# MCU_INTERFACE.net
KiCad netlist of a schematic drawn in Altium Designer
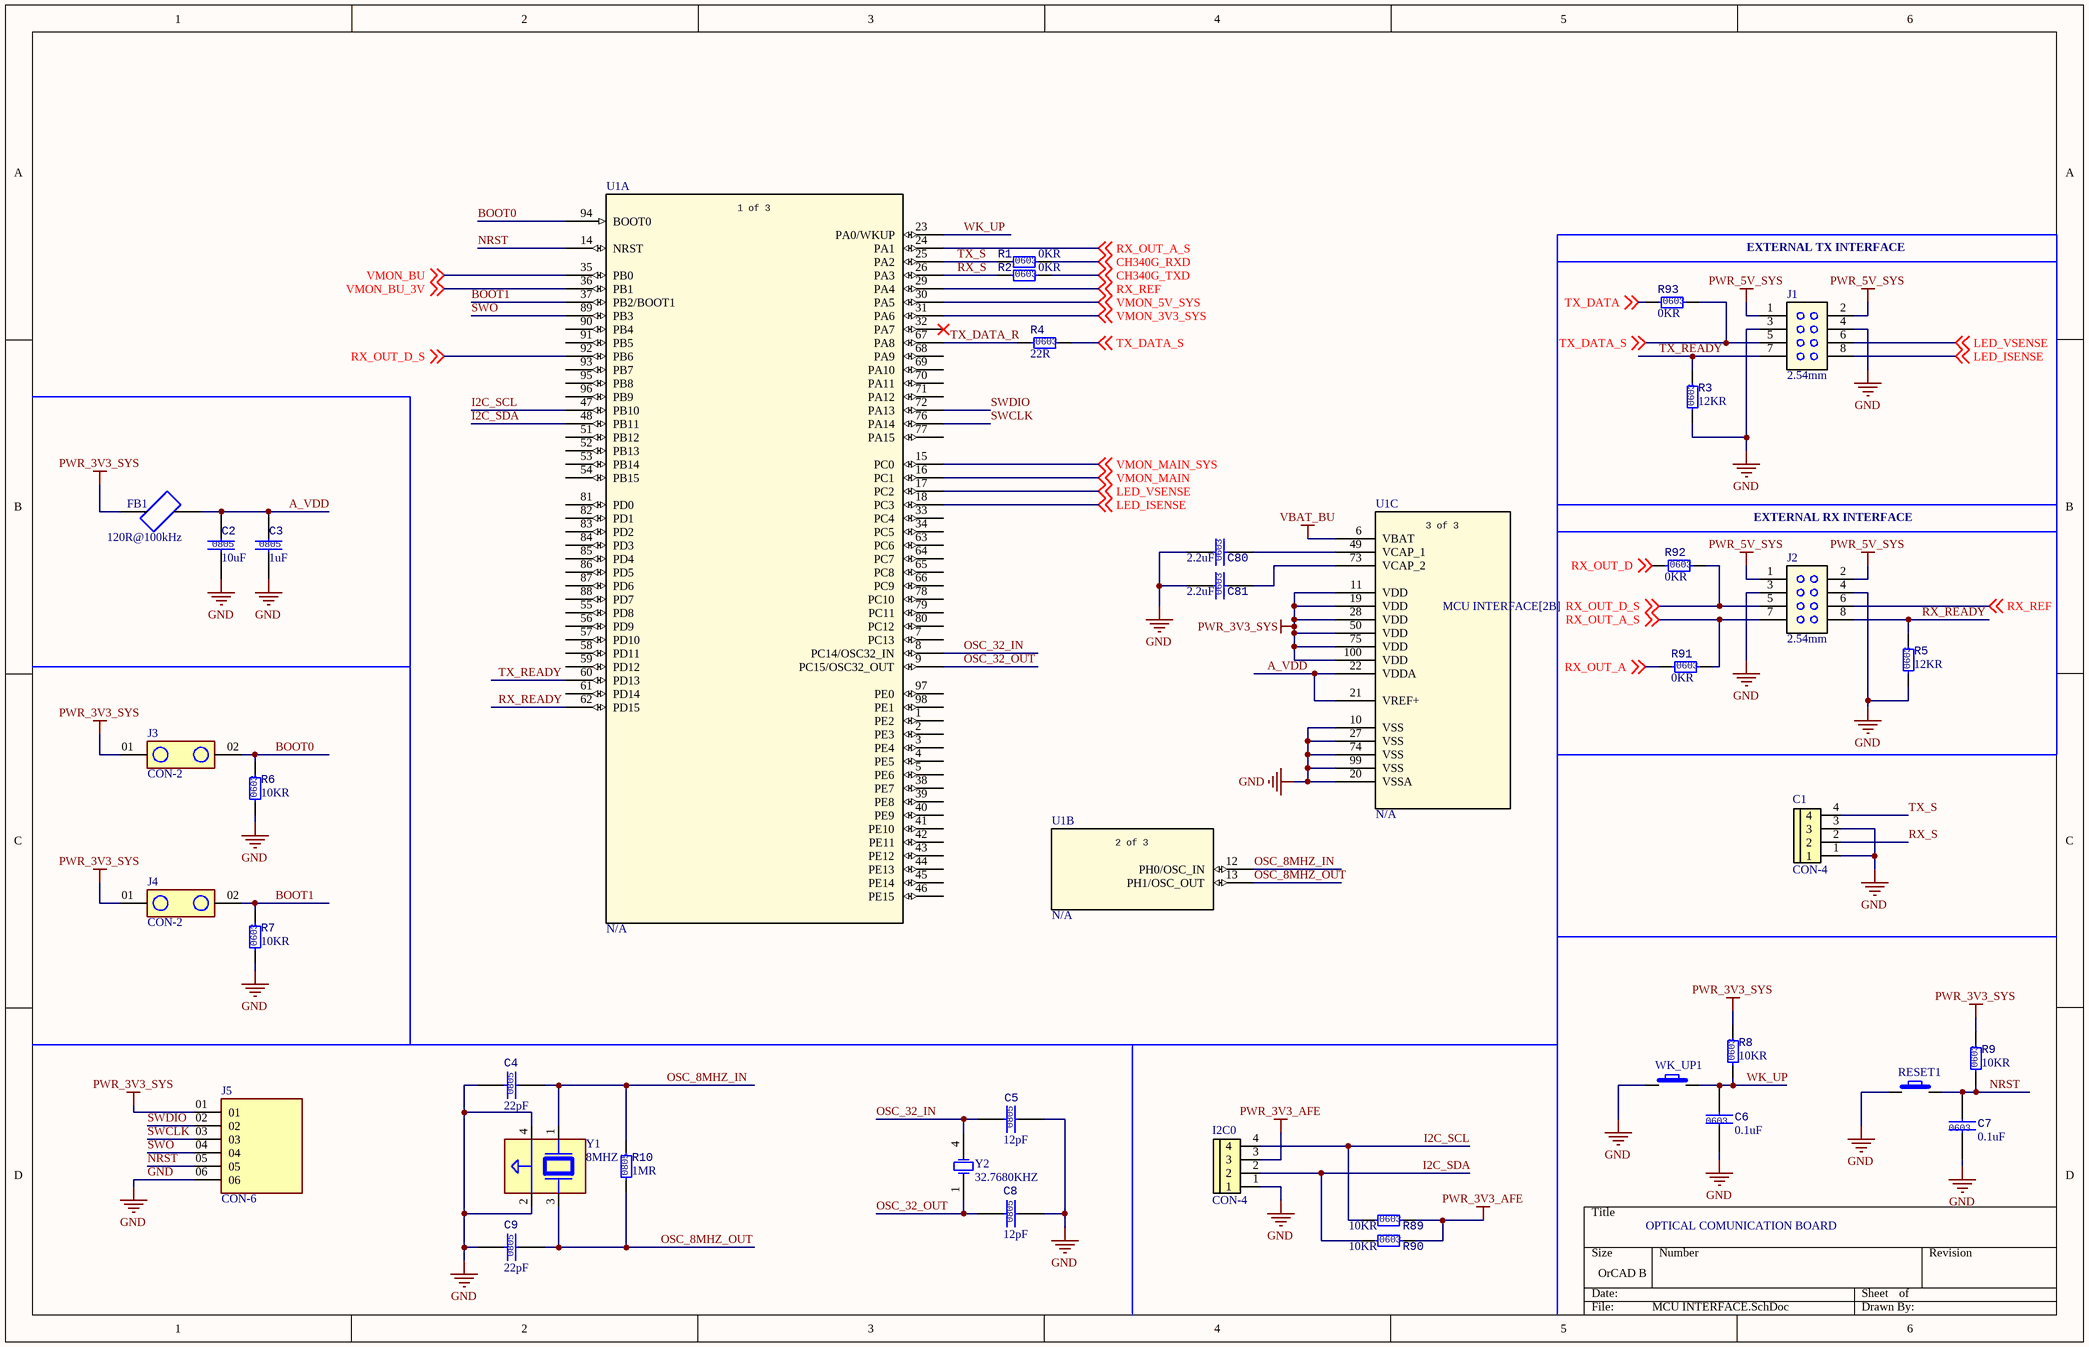
[diagram p0: MCU INTERFACE.SchDoc]

(export (version "E")
  (design (tool "Eeschema 10.0.6"))
  (components
    (comp (ref "C1")
      (value "CON-4")
      (footprint "CON-4")
      (description "Hàng Rào Đực Đơn 2.54mm 40 Chân 1 Hàng Cao 11.2mm Xuyên Lỗ")
      (fields (field (name "Comment") "CONNECTOR_4"))
      (libsource (lib "Database_Libs1") (part "CON-4"))
    )
    (comp (ref "C2")
      (value "10uF")
      (footprint "CAPCER 0603 SMD")
      (description "CAPACITOR SMD 10uF 25V 10% 0805")
      (fields (field (name "SIZE") "0805") (field (name "TOLERANCE") "10%"))
      (libsource (lib "Database_Libs1") (part "CAPACITOR"))
    )
    (comp (ref "C3")
      (value "1uF")
      (footprint "CAPCER 0805 SMD")
      (description "CAPACITOR SMD 1uF 16V 10% 0805")
      (fields (field (name "SIZE") "0805") (field (name "TOLERANCE") "10%"))
      (libsource (lib "Database_Libs1") (part "CAPACITOR"))
    )
    (comp (ref "C4")
      (value "22pF")
      (footprint "CAPCER 0805 SMD")
      (description "CAPACITOR SMD 22pF 50V 10% 0805")
      (fields (field (name "SIZE") "0805") (field (name "TOLERANCE") "10%") (field (name "Comment") "22uF"))
      (libsource (lib "Database_Libs1") (part "CAPACITOR"))
    )
    (comp (ref "C5")
      (value "12pF")
      (footprint "CAPCER 0805 SMD")
      (description "CAPACITOR SMD 12pF 50V 10% 0805")
      (fields (field (name "SIZE") "0805") (field (name "TOLERANCE") "10%"))
      (libsource (lib "Database_Libs1") (part "CAPACITOR"))
    )
    (comp (ref "C6")
      (value "0.1uF")
      (footprint "CAPCER 0805 SMD")
      (description "CAPACITOR SMD 0.1uF 50V 10% 0603")
      (fields (field (name "SIZE") "0603") (field (name "TOLERANCE") "10%"))
      (libsource (lib "Database_Libs1") (part "CAPACITOR"))
    )
    (comp (ref "C7")
      (value "0.1uF")
      (footprint "CAPCER 0805 SMD")
      (description "CAPACITOR SMD 0.1uF 50V 10% 0603")
      (fields (field (name "SIZE") "0603") (field (name "TOLERANCE") "10%"))
      (libsource (lib "Database_Libs1") (part "CAPACITOR"))
    )
    (comp (ref "C8")
      (value "12pF")
      (footprint "CAPCER 0805 SMD")
      (description "CAPACITOR SMD 12pF 50V 10% 0805")
      (fields (field (name "SIZE") "0805") (field (name "TOLERANCE") "10%"))
      (libsource (lib "Database_Libs1") (part "CAPACITOR"))
    )
    (comp (ref "C9")
      (value "22pF")
      (footprint "CAPCER 0805 SMD")
      (description "CAPACITOR SMD 22pF 50V 10% 0805")
      (fields (field (name "SIZE") "0805") (field (name "TOLERANCE") "10%") (field (name "Comment") "22uF"))
      (libsource (lib "Database_Libs1") (part "CAPACITOR"))
    )
    (comp (ref "C80")
      (value "2.2uF")
      (footprint "CAPCER 0603 SMD")
      (fields (field (name "SIZE") "0603"))
      (libsource (lib "Database_Libs2") (part "CAPACITOR"))
    )
    (comp (ref "C81")
      (value "2.2uF")
      (footprint "CAPCER 0603 SMD")
      (fields (field (name "SIZE") "0603"))
      (libsource (lib "Database_Libs2") (part "CAPACITOR"))
    )
    (comp (ref "FB1")
      (value "120R@100kHz")
      (footprint "FB 0805")
      (description "CBW201209U121T Ferrite Beads 2A 120 Ohm 0805")
      (libsource (lib "Database_Libs1") (part "FB"))
    )
    (comp (ref "I2C0")
      (value "CON-4")
      (footprint "CON-4")
      (description "Hàng Rào Đực Đơn 2.54mm 40 Chân 1 Hàng Cao 11.2mm Xuyên Lỗ")
      (fields (field (name "Comment") "CONNECTOR_4"))
      (libsource (lib "Database_Libs1") (part "CON-4"))
    )
    (comp (ref "J1")
      (value "2.54mm")
      (footprint "HD_2X4_2P54_M_V")
      (fields (field (name "Comment") "HD_2X4_M_V"))
      (libsource (lib "Database_Libs2") (part "HD_2X4_8POS"))
    )
    (comp (ref "J2")
      (value "2.54mm")
      (footprint "HD_2X4_2P54_M_V")
      (fields (field (name "Comment") "HD_2X4_M_V"))
      (libsource (lib "Database_Libs2") (part "HD_2X4_8POS"))
    )
    (comp (ref "J3")
      (value "CON-2")
      (footprint "CON-2")
      (description "Hàng Rào Đực Đơn 2.54mm 40 Chân 1 Hàng Cao 11.2mm Xuyên Lỗ")
      (fields (field (name "Comment") "CONNECTOR_2"))
      (libsource (lib "Database_Libs1") (part "CON-2"))
    )
    (comp (ref "J4")
      (value "CON-2")
      (footprint "CON-2")
      (description "Hàng Rào Đực Đơn 2.54mm 40 Chân 1 Hàng Cao 11.2mm Xuyên Lỗ")
      (fields (field (name "Comment") "CONNECTOR_2"))
      (libsource (lib "Database_Libs1") (part "CON-2"))
    )
    (comp (ref "J5")
      (value "CON-6")
      (footprint "CON-6")
      (description "Hàng Rào Đực Đơn 2.54mm 40 Chân 1 Hàng Cao 11.2mm Xuyên Lỗ")
      (fields (field (name "Comment") "CONNECTOR_6"))
      (libsource (lib "Database_Libs1") (part "CON-6"))
    )
    (comp (ref "R1")
      (value "0KR")
      (footprint "RESC 0603(1608) SMD")
      (description "RESISTOR SMD 0KR OHM 1% 100mW 0603")
      (fields (field (name "SIZE") "0603") (field (name "TOLERANCE") "1%") (field (name "Comment") "0R"))
      (libsource (lib "Database_Libs1") (part "RESISTOR"))
    )
    (comp (ref "R2")
      (value "0KR")
      (footprint "RESC 0603(1608) SMD")
      (description "RESISTOR SMD 0KR OHM 1% 100mW 0603")
      (fields (field (name "SIZE") "0603") (field (name "TOLERANCE") "1%") (field (name "Comment") "0R"))
      (libsource (lib "Database_Libs1") (part "RESISTOR"))
    )
    (comp (ref "R3")
      (value "12KR")
      (footprint "RESC 0603(1608) SMD")
      (description "RESISTOR SMD 12KR OHM 1% 100mW 0603")
      (fields (field (name "SIZE") "0603") (field (name "TOLERANCE") "1%"))
      (libsource (lib "") (part "RESISTOR_1"))
    )
    (comp (ref "R4")
      (value "22R")
      (footprint "RESC 0603(1608) SMD")
      (fields (field (name "SIZE") "0603"))
      (libsource (lib "Database_Libs2") (part "RESISTOR"))
    )
    (comp (ref "R5")
      (value "12KR")
      (footprint "RESC 0603(1608) SMD")
      (description "RESISTOR SMD 12KR OHM 1% 100mW 0603")
      (fields (field (name "SIZE") "0603") (field (name "TOLERANCE") "1%"))
      (libsource (lib "") (part "RESISTOR_1"))
    )
    (comp (ref "R6")
      (value "10KR")
      (footprint "RESC 0603(1608) SMD")
      (description "RESISTOR SMD 10KR OHM 1% 100mW 0603")
      (fields (field (name "SIZE") "0603") (field (name "TOLERANCE") "1%"))
      (libsource (lib "") (part "RESISTOR_1"))
    )
    (comp (ref "R7")
      (value "10KR")
      (footprint "RESC 0603(1608) SMD")
      (description "RESISTOR SMD 10KR OHM 1% 100mW 0603")
      (fields (field (name "SIZE") "0603") (field (name "TOLERANCE") "1%"))
      (libsource (lib "") (part "RESISTOR_1"))
    )
    (comp (ref "R8")
      (value "10KR")
      (footprint "RESC 0603(1608) SMD")
      (description "RESISTOR SMD 10KR OHM 1% 100mW 0603")
      (fields (field (name "SIZE") "0603") (field (name "TOLERANCE") "1%"))
      (libsource (lib "") (part "RESISTOR_1"))
    )
    (comp (ref "R9")
      (value "10KR")
      (footprint "RESC 0603(1608) SMD")
      (description "RESISTOR SMD 10KR OHM 1% 100mW 0603")
      (fields (field (name "SIZE") "0603") (field (name "TOLERANCE") "1%"))
      (libsource (lib "") (part "RESISTOR_1"))
    )
    (comp (ref "R10")
      (value "1MR")
      (footprint "CAPCER 0805 SMD")
      (description "RESISTOR SMD 1 MOHM 1% 100mW 0805")
      (fields
        (field (name "SIZE") "0805")
        (field (name "TOLERANCE") "1%")
        (field (name "Comment") "Điện Trở 1 MOhm 0805 1%")
      )
      (libsource (lib "") (part "RESISTOR_1"))
    )
    (comp (ref "R89")
      (value "10KR")
      (footprint "RESC 0603(1608) SMD")
      (description "RESISTOR SMD 10KR OHM 1% 100mW 0603")
      (fields (field (name "SIZE") "0603") (field (name "TOLERANCE") "1%"))
      (libsource (lib "Database_Libs1") (part "RESISTOR"))
    )
    (comp (ref "R90")
      (value "10KR")
      (footprint "RESC 0603(1608) SMD")
      (description "RESISTOR SMD 10KR OHM 1% 100mW 0603")
      (fields (field (name "SIZE") "0603") (field (name "TOLERANCE") "1%"))
      (libsource (lib "Database_Libs1") (part "RESISTOR"))
    )
    (comp (ref "R91")
      (value "0KR")
      (footprint "RESC 0603(1608) SMD")
      (description "RESISTOR SMD 0KR OHM 1% 100mW 0603")
      (fields (field (name "SIZE") "0603") (field (name "TOLERANCE") "1%") (field (name "Comment") "0R"))
      (libsource (lib "Database_Libs1") (part "RESISTOR"))
    )
    (comp (ref "R92")
      (value "0KR")
      (footprint "RESC 0603(1608) SMD")
      (description "RESISTOR SMD 0KR OHM 1% 100mW 0603")
      (fields (field (name "SIZE") "0603") (field (name "TOLERANCE") "1%") (field (name "Comment") "0R"))
      (libsource (lib "Database_Libs1") (part "RESISTOR"))
    )
    (comp (ref "R93")
      (value "0KR")
      (footprint "RESC 0603(1608) SMD")
      (description "RESISTOR SMD 0KR OHM 1% 100mW 0603")
      (fields (field (name "SIZE") "0603") (field (name "TOLERANCE") "1%") (field (name "Comment") "0R"))
      (libsource (lib "Database_Libs1") (part "RESISTOR"))
    )
    (comp (ref "RESET1")
      (value "BUTTON")
      (footprint "BUTTON_SMD")
      (description "Nút Nhấn 4x4mm Cao 1.5mm 4 Chân SMD Chống Nước")
      (libsource (lib "Database_Libs1") (part "BUTTON_SMD"))
    )
    (comp (ref "U1")
      (value "N/A")
      (footprint "100LQFP")
      (description "IC MCU 32BIT 512KB FLASH 100LQFP")
      (fields (field (name "Comment") "STM32F407VET6"))
      (libsource (lib "Database_Libs1") (part "STM32F407VET6"))
    )
    (comp (ref "WK_UP1")
      (value "BUTTON")
      (footprint "BUTTON_SMD")
      (description "Nút Nhấn 4x4mm Cao 1.5mm 4 Chân SMD Chống Nước")
      (libsource (lib "Database_Libs1") (part "BUTTON_SMD"))
    )
    (comp (ref "Y1")
      (value "8MHZ")
      (footprint "XTAL_5032")
      (fields (field (name "Comment") "XTAL_8Mhz"))
      (libsource (lib "Database_Libs2") (part "XTAL_12MHZ"))
    )
    (comp (ref "Y2")
      (value "32.7680KHZ")
      (footprint "4-SOJ")
      (description "CRYSTAL 32.7680KHZ 12.5PF SMD")
      (fields (field (name "Comment") "XTAL_32.786K"))
      (libsource (lib "Database_Libs1") (part "XTAL_4"))
    )
  )
  (nets
    (net (code "2") (name "/A_VDD") (class "Default")
      (node (ref "C2") (pin "1") (pinfunction "1_1") (pintype "passive"))
      (node (ref "C3") (pin "1") (pinfunction "1_1") (pintype "passive"))
      (node (ref "FB1") (pin "2") (pinfunction "2_2") (pintype "passive"))
      (node (ref "U1") (pin "21") (pinfunction "VREF+_21") (pintype "power_in"))
      (node (ref "U1") (pin "22") (pinfunction "VDDA_22") (pintype "power_in"))
    )
    (net (code "3") (name "/BOOT0") (class "Default")
      (node (ref "J3") (pin "02") (pinfunction "02_02") (pintype "passive"))
      (node (ref "R6") (pin "2") (pinfunction "2_2") (pintype "passive"))
      (node (ref "U1") (pin "94") (pinfunction "BOOT0_94") (pintype "input"))
    )
    (net (code "4") (name "/BOOT1") (class "Default")
      (node (ref "J4") (pin "02") (pinfunction "02_02") (pintype "passive"))
      (node (ref "R7") (pin "2") (pinfunction "2_2") (pintype "passive"))
      (node (ref "U1") (pin "37") (pinfunction "PB2/BOOT1_37") (pintype "bidirectional"))
    )
    (net (code "5") (name "/I2C_SCL") (class "Default")
      (node (ref "I2C0") (pin "4") (pinfunction "4_4") (pintype "passive"))
      (node (ref "R89") (pin "1") (pinfunction "1_1") (pintype "passive"))
      (node (ref "U1") (pin "47") (pinfunction "PB10_47") (pintype "bidirectional"))
    )
    (net (code "6") (name "/I2C_SDA") (class "Default")
      (node (ref "I2C0") (pin "2") (pinfunction "2_2") (pintype "passive"))
      (node (ref "R90") (pin "1") (pinfunction "1_1") (pintype "passive"))
      (node (ref "U1") (pin "48") (pinfunction "PB11_48") (pintype "bidirectional"))
    )
    (net (code "7") (name "/NRST") (class "Default")
      (node (ref "C7") (pin "2") (pinfunction "2_2") (pintype "passive"))
      (node (ref "J5") (pin "05") (pinfunction "05_05") (pintype "passive"))
      (node (ref "R9") (pin "1") (pinfunction "1_1") (pintype "passive"))
      (node (ref "RESET1") (pin "2") (pinfunction "2_2") (pintype "passive"))
      (node (ref "U1") (pin "14") (pinfunction "NRST_14") (pintype "bidirectional"))
    )
    (net (code "8") (name "/OSC_8MHZ_IN") (class "Default")
      (node (ref "C4") (pin "2") (pinfunction "2_2") (pintype "passive"))
      (node (ref "R10") (pin "2") (pinfunction "2_2") (pintype "passive"))
      (node (ref "U1") (pin "12") (pinfunction "PH0/OSC_IN_12") (pintype "bidirectional"))
      (node (ref "Y1") (pin "1") (pinfunction "1_1") (pintype "passive"))
    )
    (net (code "9") (name "/OSC_8MHZ_OUT") (class "Default")
      (node (ref "C9") (pin "2") (pinfunction "2_2") (pintype "passive"))
      (node (ref "R10") (pin "1") (pinfunction "1_1") (pintype "passive"))
      (node (ref "U1") (pin "13") (pinfunction "PH1/OSC_OUT_13") (pintype "bidirectional"))
      (node (ref "Y1") (pin "3") (pinfunction "2_3") (pintype "passive"))
    )
    (net (code "10") (name "/OSC_32_IN") (class "Default")
      (node (ref "C5") (pin "1") (pinfunction "1_1") (pintype "passive"))
      (node (ref "U1") (pin "8") (pinfunction "PC14/OSC32_IN_8") (pintype "bidirectional"))
      (node (ref "Y2") (pin "4") (pinfunction "OSC2_4") (pintype "passive"))
    )
    (net (code "11") (name "/OSC_32_OUT") (class "Default")
      (node (ref "C8") (pin "1") (pinfunction "1_1") (pintype "passive"))
      (node (ref "U1") (pin "9") (pinfunction "PC15/OSC32_OUT_9") (pintype "bidirectional"))
      (node (ref "Y2") (pin "1") (pinfunction "OSC1_1") (pintype "passive"))
    )
    (net (code "12") (name "/RX_READY") (class "Default")
      (node (ref "J2") (pin "8") (pinfunction "8_8") (pintype "passive"))
      (node (ref "R5") (pin "2") (pinfunction "2_2") (pintype "passive"))
      (node (ref "U1") (pin "62") (pinfunction "PD15_62") (pintype "bidirectional"))
    )
    (net (code "13") (name "/RX_S") (class "Default")
      (node (ref "C1") (pin "2") (pinfunction "2_2") (pintype "passive"))
      (node (ref "R2") (pin "1") (pinfunction "1_1") (pintype "passive"))
      (node (ref "U1") (pin "26") (pinfunction "PA3_26") (pintype "bidirectional"))
    )
    (net (code "14") (name "/SWCLK") (class "Default")
      (node (ref "J5") (pin "03") (pinfunction "03_03") (pintype "passive"))
      (node (ref "U1") (pin "76") (pinfunction "PA14_76") (pintype "bidirectional"))
    )
    (net (code "15") (name "/SWDIO") (class "Default")
      (node (ref "J5") (pin "02") (pinfunction "02_02") (pintype "passive"))
      (node (ref "U1") (pin "72") (pinfunction "PA13_72") (pintype "bidirectional"))
    )
    (net (code "16") (name "/SWO") (class "Default")
      (node (ref "J5") (pin "04") (pinfunction "04_04") (pintype "passive"))
      (node (ref "U1") (pin "89") (pinfunction "PB3_89") (pintype "bidirectional"))
    )
    (net (code "17") (name "/TX_DATA_R") (class "Default")
      (node (ref "R4") (pin "1") (pinfunction "1_1") (pintype "passive"))
      (node (ref "U1") (pin "67") (pinfunction "PA8_67") (pintype "bidirectional"))
    )
    (net (code "18") (name "/TX_READY") (class "Default")
      (node (ref "J1") (pin "7") (pinfunction "7_7") (pintype "passive"))
      (node (ref "R3") (pin "2") (pinfunction "2_2") (pintype "passive"))
      (node (ref "U1") (pin "60") (pinfunction "PD13_60") (pintype "bidirectional"))
    )
    (net (code "19") (name "/TX_S") (class "Default")
      (node (ref "C1") (pin "4") (pinfunction "4_4") (pintype "passive"))
      (node (ref "R1") (pin "1") (pinfunction "1_1") (pintype "passive"))
      (node (ref "U1") (pin "25") (pinfunction "PA2_25") (pintype "bidirectional"))
    )
    (net (code "20") (name "/WK_UP") (class "Default")
      (node (ref "C6") (pin "2") (pinfunction "2_2") (pintype "passive"))
      (node (ref "R8") (pin "1") (pinfunction "1_1") (pintype "passive"))
      (node (ref "U1") (pin "23") (pinfunction "PA0/WKUP_23") (pintype "bidirectional"))
      (node (ref "WK_UP1") (pin "2") (pinfunction "2_2") (pintype "passive"))
    )
    (net (code "21") (name "CH340G_RXD") (class "Default")
      (node (ref "R1") (pin "2") (pinfunction "2_2") (pintype "passive"))
    )
    (net (code "22") (name "CH340G_TXD") (class "Default")
      (node (ref "R2") (pin "2") (pinfunction "2_2") (pintype "passive"))
    )
    (net (code "23") (name "GND") (class "Default")
      (node (ref "C1") (pin "1") (pinfunction "1_1") (pintype "passive"))
      (node (ref "C1") (pin "3") (pinfunction "3_3") (pintype "passive"))
      (node (ref "C2") (pin "2") (pinfunction "2_2") (pintype "passive"))
      (node (ref "C3") (pin "2") (pinfunction "2_2") (pintype "passive"))
      (node (ref "C4") (pin "1") (pinfunction "1_1") (pintype "passive"))
      (node (ref "C5") (pin "2") (pinfunction "2_2") (pintype "passive"))
      (node (ref "C6") (pin "1") (pinfunction "1_1") (pintype "passive"))
      (node (ref "C7") (pin "1") (pinfunction "1_1") (pintype "passive"))
      (node (ref "C8") (pin "2") (pinfunction "2_2") (pintype "passive"))
      (node (ref "C80") (pin "1") (pinfunction "1_1") (pintype "passive"))
      (node (ref "C81") (pin "1") (pinfunction "1_1") (pintype "passive"))
      (node (ref "C9") (pin "1") (pinfunction "1_1") (pintype "passive"))
      (node (ref "I2C0") (pin "1") (pinfunction "1_1") (pintype "passive"))
      (node (ref "J1") (pin "3") (pinfunction "3_3") (pintype "passive"))
      (node (ref "J1") (pin "4") (pinfunction "4_4") (pintype "passive"))
      (node (ref "J2") (pin "3") (pinfunction "3_3") (pintype "passive"))
      (node (ref "J2") (pin "4") (pinfunction "4_4") (pintype "passive"))
      (node (ref "J5") (pin "06") (pinfunction "06_06") (pintype "passive"))
      (node (ref "R3") (pin "1") (pinfunction "1_1") (pintype "passive"))
      (node (ref "R5") (pin "1") (pinfunction "1_1") (pintype "passive"))
      (node (ref "R6") (pin "1") (pinfunction "1_1") (pintype "passive"))
      (node (ref "R7") (pin "1") (pinfunction "1_1") (pintype "passive"))
      (node (ref "RESET1") (pin "1") (pinfunction "1_1") (pintype "passive"))
      (node (ref "U1") (pin "10") (pinfunction "VSS_10") (pintype "power_in"))
      (node (ref "U1") (pin "20") (pinfunction "VSSA_20") (pintype "power_in"))
      (node (ref "U1") (pin "27") (pinfunction "VSS_27") (pintype "power_in"))
      (node (ref "U1") (pin "74") (pinfunction "VSS_74") (pintype "power_in"))
      (node (ref "U1") (pin "99") (pinfunction "VSS_99") (pintype "power_in"))
      (node (ref "WK_UP1") (pin "1") (pinfunction "1_1") (pintype "passive"))
      (node (ref "Y1") (pin "2") (pinfunction "GND_2") (pintype "power_in"))
      (node (ref "Y1") (pin "4") (pinfunction "GND_4") (pintype "passive"))
    )
    (net (code "24") (name "LED_ISENSE") (class "Default")
      (node (ref "J1") (pin "8") (pinfunction "8_8") (pintype "passive"))
      (node (ref "U1") (pin "18") (pinfunction "PC3_18") (pintype "bidirectional"))
    )
    (net (code "25") (name "LED_VSENSE") (class "Default")
      (node (ref "J1") (pin "6") (pinfunction "6_6") (pintype "passive"))
      (node (ref "U1") (pin "17") (pinfunction "PC2_17") (pintype "bidirectional"))
    )
    (net (code "26") (name "Net-(U1C-VCAP_1)") (class "Default")
      (node (ref "C80") (pin "2") (pinfunction "2_2") (pintype "passive"))
      (node (ref "U1") (pin "49") (pinfunction "VCAP_1_49") (pintype "power_in"))
    )
    (net (code "27") (name "Net-(U1C-VCAP_2)") (class "Default")
      (node (ref "C81") (pin "2") (pinfunction "2_2") (pintype "passive"))
      (node (ref "U1") (pin "73") (pinfunction "VCAP_2_73") (pintype "power_in"))
    )
    (net (code "28") (name "PWR_3V3_AFE") (class "Default")
      (node (ref "I2C0") (pin "3") (pinfunction "3_3") (pintype "passive"))
      (node (ref "R89") (pin "2") (pinfunction "2_2") (pintype "passive"))
      (node (ref "R90") (pin "2") (pinfunction "2_2") (pintype "passive"))
    )
    (net (code "29") (name "PWR_3V3_SYS") (class "Default")
      (node (ref "FB1") (pin "1") (pinfunction "1_1") (pintype "passive"))
      (node (ref "J3") (pin "01") (pinfunction "01_01") (pintype "passive"))
      (node (ref "J4") (pin "01") (pinfunction "01_01") (pintype "passive"))
      (node (ref "J5") (pin "01") (pinfunction "01_01") (pintype "passive"))
      (node (ref "R8") (pin "2") (pinfunction "2_2") (pintype "passive"))
      (node (ref "R9") (pin "2") (pinfunction "2_2") (pintype "passive"))
      (node (ref "U1") (pin "100") (pinfunction "VDD_100") (pintype "power_in"))
      (node (ref "U1") (pin "11") (pinfunction "VDD_11") (pintype "power_in"))
      (node (ref "U1") (pin "19") (pinfunction "VDD_19") (pintype "power_in"))
      (node (ref "U1") (pin "28") (pinfunction "VDD_28") (pintype "power_in"))
      (node (ref "U1") (pin "50") (pinfunction "VDD_50") (pintype "power_in"))
      (node (ref "U1") (pin "75") (pinfunction "VDD_75") (pintype "power_in"))
    )
    (net (code "30") (name "PWR_5V_SYS") (class "Default")
      (node (ref "J1") (pin "1") (pinfunction "1_1") (pintype "passive"))
      (node (ref "J1") (pin "2") (pinfunction "2_2") (pintype "passive"))
      (node (ref "J2") (pin "1") (pinfunction "1_1") (pintype "passive"))
      (node (ref "J2") (pin "2") (pinfunction "2_2") (pintype "passive"))
    )
    (net (code "31") (name "RX_OUT_A") (class "Default")
      (node (ref "R91") (pin "1") (pinfunction "1_1") (pintype "passive"))
    )
    (net (code "32") (name "RX_OUT_A_S") (class "Default")
      (node (ref "J2") (pin "7") (pinfunction "7_7") (pintype "passive"))
      (node (ref "R91") (pin "2") (pinfunction "2_2") (pintype "passive"))
      (node (ref "U1") (pin "24") (pinfunction "PA1_24") (pintype "bidirectional"))
    )
    (net (code "33") (name "RX_OUT_D") (class "Default")
      (node (ref "R92") (pin "1") (pinfunction "1_1") (pintype "passive"))
    )
    (net (code "34") (name "RX_OUT_D_S") (class "Default")
      (node (ref "J2") (pin "5") (pinfunction "5_5") (pintype "passive"))
      (node (ref "R92") (pin "2") (pinfunction "2_2") (pintype "passive"))
      (node (ref "U1") (pin "92") (pinfunction "PB6_92") (pintype "bidirectional"))
    )
    (net (code "35") (name "RX_REF") (class "Default")
      (node (ref "J2") (pin "6") (pinfunction "6_6") (pintype "passive"))
      (node (ref "U1") (pin "29") (pinfunction "PA4_29") (pintype "bidirectional"))
    )
    (net (code "36") (name "TX_DATA") (class "Default")
      (node (ref "R93") (pin "1") (pinfunction "1_1") (pintype "passive"))
    )
    (net (code "37") (name "TX_DATA_S") (class "Default")
      (node (ref "J1") (pin "5") (pinfunction "5_5") (pintype "passive"))
      (node (ref "R4") (pin "2") (pinfunction "2_2") (pintype "passive"))
      (node (ref "R93") (pin "2") (pinfunction "2_2") (pintype "passive"))
    )
    (net (code "38") (name "VBAT_BU") (class "Default")
      (node (ref "U1") (pin "6") (pinfunction "VBAT_6") (pintype "power_in"))
    )
    (net (code "39") (name "VMON_3V3_SYS") (class "Default")
      (node (ref "U1") (pin "31") (pinfunction "PA6_31") (pintype "bidirectional"))
    )
    (net (code "40") (name "VMON_5V_SYS") (class "Default")
      (node (ref "U1") (pin "30") (pinfunction "PA5_30") (pintype "bidirectional"))
    )
    (net (code "41") (name "VMON_BU") (class "Default")
      (node (ref "U1") (pin "35") (pinfunction "PB0_35") (pintype "bidirectional"))
    )
    (net (code "42") (name "VMON_BU_3V") (class "Default")
      (node (ref "U1") (pin "36") (pinfunction "PB1_36") (pintype "bidirectional"))
    )
    (net (code "43") (name "VMON_MAIN") (class "Default")
      (node (ref "U1") (pin "16") (pinfunction "PC1_16") (pintype "bidirectional"))
    )
    (net (code "44") (name "VMON_MAIN_SYS") (class "Default")
      (node (ref "U1") (pin "15") (pinfunction "PC0_15") (pintype "bidirectional"))
    )
    (net (code "45") (name "unconnected-(U1A-PA7-Pad32)") (class "Default")
      (node (ref "U1") (pin "32") (pinfunction "PA7_32") (pintype "bidirectional+no_connect"))
    )
    (net (code "46") (name "unconnected-(U1A-PA9-Pad68)") (class "Default")
      (node (ref "U1") (pin "68") (pinfunction "PA9_68") (pintype "bidirectional"))
    )
    (net (code "47") (name "unconnected-(U1A-PA10-Pad69)") (class "Default")
      (node (ref "U1") (pin "69") (pinfunction "PA10_69") (pintype "bidirectional"))
    )
    (net (code "48") (name "unconnected-(U1A-PA11-Pad70)") (class "Default")
      (node (ref "U1") (pin "70") (pinfunction "PA11_70") (pintype "bidirectional"))
    )
    (net (code "49") (name "unconnected-(U1A-PA12-Pad71)") (class "Default")
      (node (ref "U1") (pin "71") (pinfunction "PA12_71") (pintype "bidirectional"))
    )
    (net (code "50") (name "unconnected-(U1A-PA15-Pad77)") (class "Default")
      (node (ref "U1") (pin "77") (pinfunction "PA15_77") (pintype "bidirectional"))
    )
    (net (code "51") (name "unconnected-(U1A-PB4-Pad90)") (class "Default")
      (node (ref "U1") (pin "90") (pinfunction "PB4_90") (pintype "bidirectional"))
    )
    (net (code "52") (name "unconnected-(U1A-PB5-Pad91)") (class "Default")
      (node (ref "U1") (pin "91") (pinfunction "PB5_91") (pintype "bidirectional"))
    )
    (net (code "53") (name "unconnected-(U1A-PB7-Pad93)") (class "Default")
      (node (ref "U1") (pin "93") (pinfunction "PB7_93") (pintype "bidirectional"))
    )
    (net (code "54") (name "unconnected-(U1A-PB8-Pad95)") (class "Default")
      (node (ref "U1") (pin "95") (pinfunction "PB8_95") (pintype "bidirectional"))
    )
    (net (code "55") (name "unconnected-(U1A-PB9-Pad96)") (class "Default")
      (node (ref "U1") (pin "96") (pinfunction "PB9_96") (pintype "bidirectional"))
    )
    (net (code "56") (name "unconnected-(U1A-PB12-Pad51)") (class "Default")
      (node (ref "U1") (pin "51") (pinfunction "PB12_51") (pintype "bidirectional"))
    )
    (net (code "57") (name "unconnected-(U1A-PB13-Pad52)") (class "Default")
      (node (ref "U1") (pin "52") (pinfunction "PB13_52") (pintype "bidirectional"))
    )
    (net (code "58") (name "unconnected-(U1A-PB14-Pad53)") (class "Default")
      (node (ref "U1") (pin "53") (pinfunction "PB14_53") (pintype "bidirectional"))
    )
    (net (code "59") (name "unconnected-(U1A-PB15-Pad54)") (class "Default")
      (node (ref "U1") (pin "54") (pinfunction "PB15_54") (pintype "bidirectional"))
    )
    (net (code "60") (name "unconnected-(U1A-PC4-Pad33)") (class "Default")
      (node (ref "U1") (pin "33") (pinfunction "PC4_33") (pintype "bidirectional"))
    )
    (net (code "61") (name "unconnected-(U1A-PC5-Pad34)") (class "Default")
      (node (ref "U1") (pin "34") (pinfunction "PC5_34") (pintype "bidirectional"))
    )
    (net (code "62") (name "unconnected-(U1A-PC6-Pad63)") (class "Default")
      (node (ref "U1") (pin "63") (pinfunction "PC6_63") (pintype "bidirectional"))
    )
    (net (code "63") (name "unconnected-(U1A-PC7-Pad64)") (class "Default")
      (node (ref "U1") (pin "64") (pinfunction "PC7_64") (pintype "bidirectional"))
    )
    (net (code "64") (name "unconnected-(U1A-PC8-Pad65)") (class "Default")
      (node (ref "U1") (pin "65") (pinfunction "PC8_65") (pintype "bidirectional"))
    )
    (net (code "65") (name "unconnected-(U1A-PC9-Pad66)") (class "Default")
      (node (ref "U1") (pin "66") (pinfunction "PC9_66") (pintype "bidirectional"))
    )
    (net (code "66") (name "unconnected-(U1A-PC10-Pad78)") (class "Default")
      (node (ref "U1") (pin "78") (pinfunction "PC10_78") (pintype "bidirectional"))
    )
    (net (code "67") (name "unconnected-(U1A-PC11-Pad79)") (class "Default")
      (node (ref "U1") (pin "79") (pinfunction "PC11_79") (pintype "bidirectional"))
    )
    (net (code "68") (name "unconnected-(U1A-PC12-Pad80)") (class "Default")
      (node (ref "U1") (pin "80") (pinfunction "PC12_80") (pintype "bidirectional"))
    )
    (net (code "69") (name "unconnected-(U1A-PC13-Pad7)") (class "Default")
      (node (ref "U1") (pin "7") (pinfunction "PC13_7") (pintype "bidirectional"))
    )
    (net (code "70") (name "unconnected-(U1A-PD0-Pad81)") (class "Default")
      (node (ref "U1") (pin "81") (pinfunction "PD0_81") (pintype "bidirectional"))
    )
    (net (code "71") (name "unconnected-(U1A-PD1-Pad82)") (class "Default")
      (node (ref "U1") (pin "82") (pinfunction "PD1_82") (pintype "bidirectional"))
    )
    (net (code "72") (name "unconnected-(U1A-PD2-Pad83)") (class "Default")
      (node (ref "U1") (pin "83") (pinfunction "PD2_83") (pintype "bidirectional"))
    )
    (net (code "73") (name "unconnected-(U1A-PD3-Pad84)") (class "Default")
      (node (ref "U1") (pin "84") (pinfunction "PD3_84") (pintype "bidirectional"))
    )
    (net (code "74") (name "unconnected-(U1A-PD4-Pad85)") (class "Default")
      (node (ref "U1") (pin "85") (pinfunction "PD4_85") (pintype "bidirectional"))
    )
    (net (code "75") (name "unconnected-(U1A-PD5-Pad86)") (class "Default")
      (node (ref "U1") (pin "86") (pinfunction "PD5_86") (pintype "bidirectional"))
    )
    (net (code "76") (name "unconnected-(U1A-PD6-Pad87)") (class "Default")
      (node (ref "U1") (pin "87") (pinfunction "PD6_87") (pintype "bidirectional"))
    )
    (net (code "77") (name "unconnected-(U1A-PD7-Pad88)") (class "Default")
      (node (ref "U1") (pin "88") (pinfunction "PD7_88") (pintype "bidirectional"))
    )
    (net (code "78") (name "unconnected-(U1A-PD8-Pad55)") (class "Default")
      (node (ref "U1") (pin "55") (pinfunction "PD8_55") (pintype "bidirectional"))
    )
    (net (code "79") (name "unconnected-(U1A-PD9-Pad56)") (class "Default")
      (node (ref "U1") (pin "56") (pinfunction "PD9_56") (pintype "bidirectional"))
    )
    (net (code "80") (name "unconnected-(U1A-PD10-Pad57)") (class "Default")
      (node (ref "U1") (pin "57") (pinfunction "PD10_57") (pintype "bidirectional"))
    )
    (net (code "81") (name "unconnected-(U1A-PD11-Pad58)") (class "Default")
      (node (ref "U1") (pin "58") (pinfunction "PD11_58") (pintype "bidirectional"))
    )
    (net (code "82") (name "unconnected-(U1A-PD12-Pad59)") (class "Default")
      (node (ref "U1") (pin "59") (pinfunction "PD12_59") (pintype "bidirectional"))
    )
    (net (code "83") (name "unconnected-(U1A-PD14-Pad61)") (class "Default")
      (node (ref "U1") (pin "61") (pinfunction "PD14_61") (pintype "bidirectional"))
    )
    (net (code "84") (name "unconnected-(U1A-PE0-Pad97)") (class "Default")
      (node (ref "U1") (pin "97") (pinfunction "PE0_97") (pintype "bidirectional"))
    )
    (net (code "85") (name "unconnected-(U1A-PE1-Pad98)") (class "Default")
      (node (ref "U1") (pin "98") (pinfunction "PE1_98") (pintype "bidirectional"))
    )
    (net (code "86") (name "unconnected-(U1A-PE2-Pad1)") (class "Default")
      (node (ref "U1") (pin "1") (pinfunction "PE2_1") (pintype "bidirectional"))
    )
    (net (code "87") (name "unconnected-(U1A-PE3-Pad2)") (class "Default")
      (node (ref "U1") (pin "2") (pinfunction "PE3_2") (pintype "bidirectional"))
    )
    (net (code "88") (name "unconnected-(U1A-PE4-Pad3)") (class "Default")
      (node (ref "U1") (pin "3") (pinfunction "PE4_3") (pintype "bidirectional"))
    )
    (net (code "89") (name "unconnected-(U1A-PE5-Pad4)") (class "Default")
      (node (ref "U1") (pin "4") (pinfunction "PE5_4") (pintype "bidirectional"))
    )
    (net (code "90") (name "unconnected-(U1A-PE6-Pad5)") (class "Default")
      (node (ref "U1") (pin "5") (pinfunction "PE6_5") (pintype "bidirectional"))
    )
    (net (code "91") (name "unconnected-(U1A-PE7-Pad38)") (class "Default")
      (node (ref "U1") (pin "38") (pinfunction "PE7_38") (pintype "bidirectional"))
    )
    (net (code "92") (name "unconnected-(U1A-PE8-Pad39)") (class "Default")
      (node (ref "U1") (pin "39") (pinfunction "PE8_39") (pintype "bidirectional"))
    )
    (net (code "93") (name "unconnected-(U1A-PE9-Pad40)") (class "Default")
      (node (ref "U1") (pin "40") (pinfunction "PE9_40") (pintype "bidirectional"))
    )
    (net (code "94") (name "unconnected-(U1A-PE10-Pad41)") (class "Default")
      (node (ref "U1") (pin "41") (pinfunction "PE10_41") (pintype "bidirectional"))
    )
    (net (code "95") (name "unconnected-(U1A-PE11-Pad42)") (class "Default")
      (node (ref "U1") (pin "42") (pinfunction "PE11_42") (pintype "bidirectional"))
    )
    (net (code "96") (name "unconnected-(U1A-PE12-Pad43)") (class "Default")
      (node (ref "U1") (pin "43") (pinfunction "PE12_43") (pintype "bidirectional"))
    )
    (net (code "97") (name "unconnected-(U1A-PE13-Pad44)") (class "Default")
      (node (ref "U1") (pin "44") (pinfunction "PE13_44") (pintype "bidirectional"))
    )
    (net (code "98") (name "unconnected-(U1A-PE14-Pad45)") (class "Default")
      (node (ref "U1") (pin "45") (pinfunction "PE14_45") (pintype "bidirectional"))
    )
    (net (code "99") (name "unconnected-(U1A-PE15-Pad46)") (class "Default")
      (node (ref "U1") (pin "46") (pinfunction "PE15_46") (pintype "bidirectional"))
    )
  )
)
